# openrex_addon_V1.net
KiCad netlist of a schematic drawn in Altium Designer
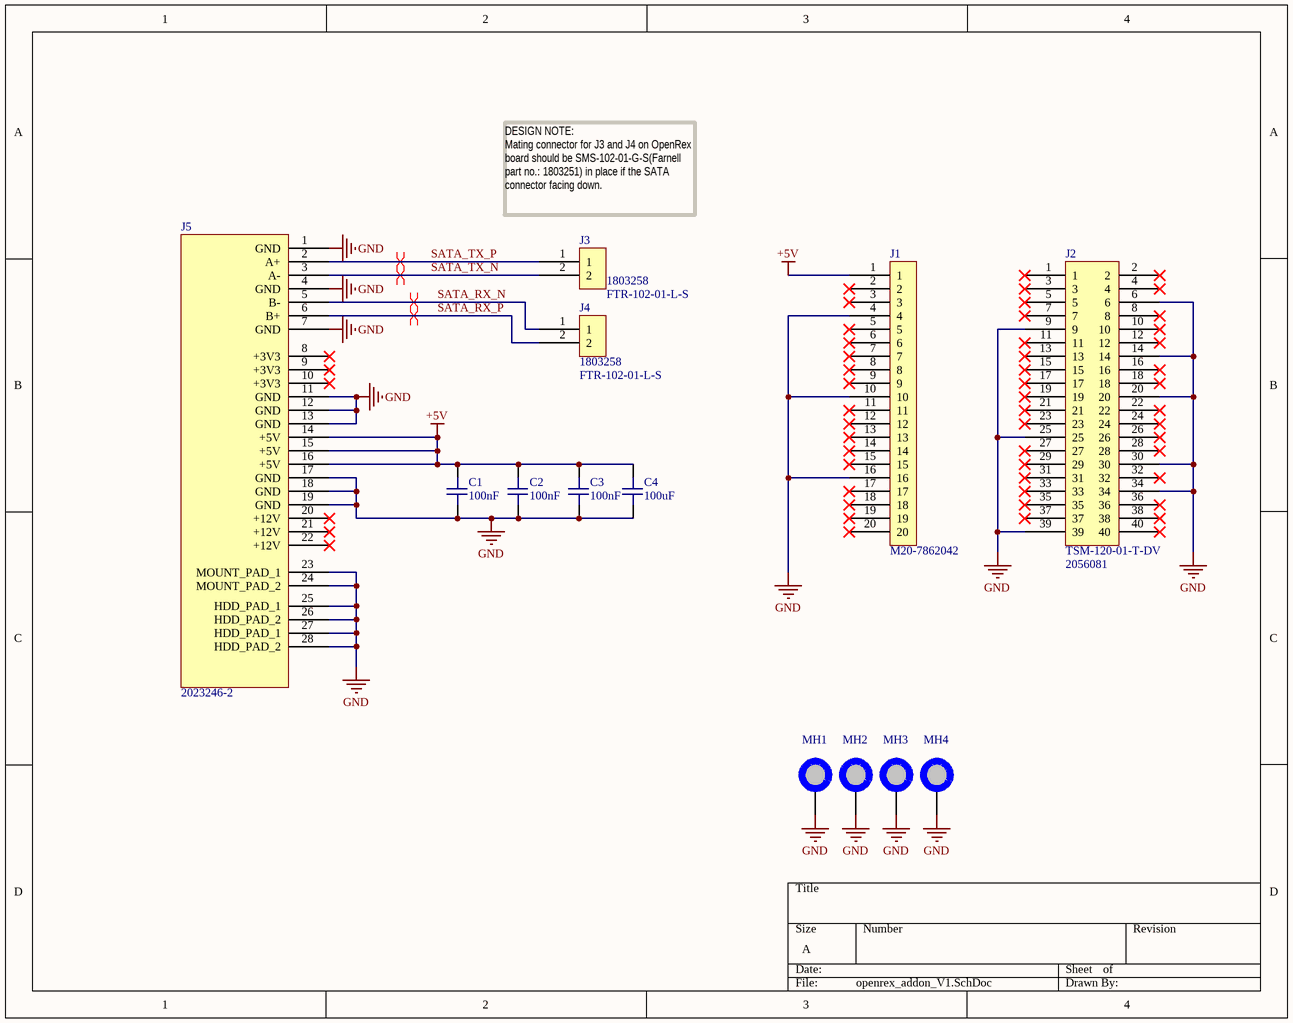
[diagram p0: openrex_addon_V1.SchDoc]

(export (version "E")
  (design (tool "Eeschema 10.0.6"))
  (components
    (comp (ref "C1")
      (value "100nF")
      (footprint "C0805")
      (description "CAP CER 0.1UF 50V X7R 0805")
      (fields
        (field (name "MANUFACTURER") "TDK Corporation")
        (field (name "MANUFACTURER PART NUMBER") "C2012X7R1H104K085AA")
      )
      (libsource (lib "openrex_addon_V1") (part "C2012X7R1H104K085AA"))
    )
    (comp (ref "C2")
      (value "100nF")
      (footprint "C0805")
      (description "CAP CER 0.1UF 50V X7R 0805")
      (fields
        (field (name "MANUFACTURER") "TDK Corporation")
        (field (name "MANUFACTURER PART NUMBER") "C2012X7R1H104K085AA")
      )
      (libsource (lib "openrex_addon_V1") (part "C2012X7R1H104K085AA"))
    )
    (comp (ref "C3")
      (value "100nF")
      (footprint "C0805")
      (description "CAP CER 0.1UF 50V X7R 0805")
      (fields
        (field (name "MANUFACTURER") "TDK Corporation")
        (field (name "MANUFACTURER PART NUMBER") "C2012X7R1H104K085AA")
      )
      (libsource (lib "openrex_addon_V1") (part "C2012X7R1H104K085AA"))
    )
    (comp (ref "C4")
      (value "100uF")
      (footprint "C1206")
      (description "CAP CER 100UF 10V X5R 1206")
      (fields
        (field (name "MANUFACTURER") "TDK Corporation")
        (field (name "MANUFACTURER PART NUMBER") "C3216X5R1A107M160AC")
      )
      (libsource (lib "openrex_addon_V1") (part "C3216X5R1A107M160AC"))
    )
    (comp (ref "J1")
      (value "M20-7862042")
      (footprint "20x1 2.54 Female SMD")
      (description "HARWIN - M20-7862042 - SOCKET, BOTTOM ENTRY, SMT, 20WAY")
      (fields (field (name "MANUFACTURER") "HARWIN"))
      (libsource (lib "openrex_addon_V1") (part "M20-7862042"))
    )
    (comp (ref "J2")
      (value "TSM-120-01-T-DV")
      (footprint "20x2 2.54 Male SMD")
      (description "CONN HEADER 40POS .100\" DBL SMD")
      (fields (field (name "MANUFACTURER") "Samtec Inc.") (field (name "SUPPLIER PART NUMBER 2") "2056081"))
      (libsource (lib "openrex_addon_V1") (part "TSM-120-01-T-DV"))
    )
    (comp (ref "J3")
      (value "FTR-102-01-L-S")
      (footprint "SATA_SIGNAL")
      (description "SMT .050'' STRIPS")
      (fields (field (name "MANUFACTURER") "Samtec Inc.") (field (name "SUPPLIER PART NUMBER 2") "1803258"))
      (libsource (lib "openrex_addon_V1") (part "FTR-102-01-L-S"))
    )
    (comp (ref "J4")
      (value "FTR-102-01-L-S")
      (footprint "SATA_SIGNAL")
      (description "SMT .050'' STRIPS")
      (fields (field (name "MANUFACTURER") "Samtec Inc.") (field (name "SUPPLIER PART NUMBER 2") "1803258"))
      (libsource (lib "openrex_addon_V1") (part "FTR-102-01-L-S"))
    )
    (comp (ref "J5")
      (value "2023246-2")
      (footprint "SATA")
      (description "CONN RECEPT SATA 22POS R/A SMD")
      (fields (field (name "MANUFACTURER") "TE Connectivity AMP Connectors"))
      (libsource (lib "openrex_addon_V1") (part "2023246-2"))
    )
    (comp (ref "MH1")
      (value "MH_7.4MMC_3.2MMD")
      (footprint "MH_7.4MMD_3.2MMD")
      (description "Mounting hole 7.4mm Diameter, 3.2 Drill")
      (libsource (lib "openrex_addon_V1") (part "MH_7.4MMC_3.2MMD"))
    )
    (comp (ref "MH2")
      (value "MH_7.4MMC_3.2MMD")
      (footprint "MH_7.4MMD_3.2MMD")
      (description "Mounting hole 7.4mm Diameter, 3.2 Drill")
      (libsource (lib "openrex_addon_V1") (part "MH_7.4MMC_3.2MMD"))
    )
    (comp (ref "MH3")
      (value "MH_7.4MMC_3.2MMD")
      (footprint "MH_7.4MMD_3.2MMD")
      (description "Mounting hole 7.4mm Diameter, 3.2 Drill")
      (libsource (lib "openrex_addon_V1") (part "MH_7.4MMC_3.2MMD"))
    )
    (comp (ref "MH4")
      (value "MH_7.4MMC_3.2MMD")
      (footprint "MH_7.4MMD_3.2MMD")
      (description "Mounting hole 7.4mm Diameter, 3.2 Drill")
      (libsource (lib "openrex_addon_V1") (part "MH_7.4MMC_3.2MMD"))
    )
  )
  (nets
    (net (code "1") (name "+5V") (class "Default")
      (node (ref "C1") (pin "2") (pinfunction "2_2") (pintype "passive"))
      (node (ref "C2") (pin "2") (pinfunction "2_2") (pintype "passive"))
      (node (ref "C3") (pin "2") (pinfunction "2_2") (pintype "passive"))
      (node (ref "C4") (pin "2") (pinfunction "2_2") (pintype "passive"))
      (node (ref "J1") (pin "1") (pinfunction "1_1") (pintype "passive"))
      (node (ref "J5") (pin "14") (pinfunction "+5V_14") (pintype "passive"))
      (node (ref "J5") (pin "15") (pinfunction "+5V_15") (pintype "passive"))
      (node (ref "J5") (pin "16") (pinfunction "+5V_16") (pintype "passive"))
    )
    (net (code "2") (name "/SATA_RX_N") (class "Default")
      (node (ref "J4") (pin "1") (pinfunction "1_1") (pintype "passive"))
      (node (ref "J5") (pin "5") (pinfunction "B-_5") (pintype "passive"))
    )
    (net (code "3") (name "/SATA_RX_P") (class "Default")
      (node (ref "J4") (pin "2") (pinfunction "2_2") (pintype "passive"))
      (node (ref "J5") (pin "6") (pinfunction "B+_6") (pintype "passive"))
    )
    (net (code "4") (name "/SATA_TX_N") (class "Default")
      (node (ref "J3") (pin "2") (pinfunction "2_2") (pintype "passive"))
      (node (ref "J5") (pin "3") (pinfunction "A-_3") (pintype "passive"))
    )
    (net (code "5") (name "/SATA_TX_P") (class "Default")
      (node (ref "J3") (pin "1") (pinfunction "1_1") (pintype "passive"))
      (node (ref "J5") (pin "2") (pinfunction "A+_2") (pintype "passive"))
    )
    (net (code "6") (name "GND") (class "Default")
      (node (ref "C1") (pin "1") (pinfunction "1_1") (pintype "passive"))
      (node (ref "C2") (pin "1") (pinfunction "1_1") (pintype "passive"))
      (node (ref "C3") (pin "1") (pinfunction "1_1") (pintype "passive"))
      (node (ref "C4") (pin "1") (pinfunction "1_1") (pintype "passive"))
      (node (ref "J1") (pin "10") (pinfunction "10_10") (pintype "passive"))
      (node (ref "J1") (pin "16") (pinfunction "16_16") (pintype "passive"))
      (node (ref "J1") (pin "4") (pinfunction "4_4") (pintype "passive"))
      (node (ref "J2") (pin "14") (pinfunction "14_14") (pintype "passive"))
      (node (ref "J2") (pin "20") (pinfunction "20_20") (pintype "passive"))
      (node (ref "J2") (pin "25") (pinfunction "25_25") (pintype "passive"))
      (node (ref "J2") (pin "30") (pinfunction "30_30") (pintype "passive"))
      (node (ref "J2") (pin "34") (pinfunction "34_34") (pintype "passive"))
      (node (ref "J2") (pin "39") (pinfunction "39_39") (pintype "passive"))
      (node (ref "J2") (pin "6") (pinfunction "6_6") (pintype "passive"))
      (node (ref "J2") (pin "9") (pinfunction "9_9") (pintype "passive"))
      (node (ref "J5") (pin "1") (pinfunction "GND_1") (pintype "passive"))
      (node (ref "J5") (pin "11") (pinfunction "GND_11") (pintype "passive"))
      (node (ref "J5") (pin "12") (pinfunction "GND_12") (pintype "passive"))
      (node (ref "J5") (pin "13") (pinfunction "GND_13") (pintype "passive"))
      (node (ref "J5") (pin "17") (pinfunction "GND_17") (pintype "passive"))
      (node (ref "J5") (pin "18") (pinfunction "GND_18") (pintype "passive"))
      (node (ref "J5") (pin "19") (pinfunction "GND_19") (pintype "passive"))
      (node (ref "J5") (pin "23") (pinfunction "MOUNT_PAD_1_23") (pintype "passive"))
      (node (ref "J5") (pin "24") (pinfunction "MOUNT_PAD_2_24") (pintype "passive"))
      (node (ref "J5") (pin "25") (pinfunction "HDD_PAD_1_25") (pintype "passive"))
      (node (ref "J5") (pin "26") (pinfunction "HDD_PAD_2_26") (pintype "passive"))
      (node (ref "J5") (pin "27") (pinfunction "HDD_PAD_1_27") (pintype "passive"))
      (node (ref "J5") (pin "28") (pinfunction "HDD_PAD_2_28") (pintype "passive"))
      (node (ref "J5") (pin "4") (pinfunction "GND_4") (pintype "passive"))
      (node (ref "J5") (pin "7") (pinfunction "GND_7") (pintype "passive"))
      (node (ref "MH1") (pin "1") (pinfunction "1_1") (pintype "passive"))
      (node (ref "MH2") (pin "1") (pinfunction "1_1") (pintype "passive"))
      (node (ref "MH3") (pin "1") (pinfunction "1_1") (pintype "passive"))
      (node (ref "MH4") (pin "1") (pinfunction "1_1") (pintype "passive"))
    )
    (net (code "7") (name "unconnected-(J1-Pad2)") (class "Default")
      (node (ref "J1") (pin "2") (pinfunction "2_2") (pintype "passive+no_connect"))
    )
    (net (code "8") (name "unconnected-(J1-Pad3)") (class "Default")
      (node (ref "J1") (pin "3") (pinfunction "3_3") (pintype "passive+no_connect"))
    )
    (net (code "9") (name "unconnected-(J1-Pad5)") (class "Default")
      (node (ref "J1") (pin "5") (pinfunction "5_5") (pintype "passive+no_connect"))
    )
    (net (code "10") (name "unconnected-(J1-Pad6)") (class "Default")
      (node (ref "J1") (pin "6") (pinfunction "6_6") (pintype "passive+no_connect"))
    )
    (net (code "11") (name "unconnected-(J1-Pad7)") (class "Default")
      (node (ref "J1") (pin "7") (pinfunction "7_7") (pintype "passive+no_connect"))
    )
    (net (code "12") (name "unconnected-(J1-Pad8)") (class "Default")
      (node (ref "J1") (pin "8") (pinfunction "8_8") (pintype "passive+no_connect"))
    )
    (net (code "13") (name "unconnected-(J1-Pad9)") (class "Default")
      (node (ref "J1") (pin "9") (pinfunction "9_9") (pintype "passive+no_connect"))
    )
    (net (code "14") (name "unconnected-(J1-Pad11)") (class "Default")
      (node (ref "J1") (pin "11") (pinfunction "11_11") (pintype "passive+no_connect"))
    )
    (net (code "15") (name "unconnected-(J1-Pad12)") (class "Default")
      (node (ref "J1") (pin "12") (pinfunction "12_12") (pintype "passive+no_connect"))
    )
    (net (code "16") (name "unconnected-(J1-Pad13)") (class "Default")
      (node (ref "J1") (pin "13") (pinfunction "13_13") (pintype "passive+no_connect"))
    )
    (net (code "17") (name "unconnected-(J1-Pad14)") (class "Default")
      (node (ref "J1") (pin "14") (pinfunction "14_14") (pintype "passive+no_connect"))
    )
    (net (code "18") (name "unconnected-(J1-Pad15)") (class "Default")
      (node (ref "J1") (pin "15") (pinfunction "15_15") (pintype "passive+no_connect"))
    )
    (net (code "19") (name "unconnected-(J1-Pad17)") (class "Default")
      (node (ref "J1") (pin "17") (pinfunction "17_17") (pintype "passive+no_connect"))
    )
    (net (code "20") (name "unconnected-(J1-Pad18)") (class "Default")
      (node (ref "J1") (pin "18") (pinfunction "18_18") (pintype "passive+no_connect"))
    )
    (net (code "21") (name "unconnected-(J1-Pad19)") (class "Default")
      (node (ref "J1") (pin "19") (pinfunction "19_19") (pintype "passive+no_connect"))
    )
    (net (code "22") (name "unconnected-(J1-Pad20)") (class "Default")
      (node (ref "J1") (pin "20") (pinfunction "20_20") (pintype "passive+no_connect"))
    )
    (net (code "23") (name "unconnected-(J2-Pad1)") (class "Default")
      (node (ref "J2") (pin "1") (pinfunction "1_1") (pintype "passive+no_connect"))
    )
    (net (code "24") (name "unconnected-(J2-Pad2)") (class "Default")
      (node (ref "J2") (pin "2") (pinfunction "2_2") (pintype "passive+no_connect"))
    )
    (net (code "25") (name "unconnected-(J2-Pad3)") (class "Default")
      (node (ref "J2") (pin "3") (pinfunction "3_3") (pintype "passive+no_connect"))
    )
    (net (code "26") (name "unconnected-(J2-Pad4)") (class "Default")
      (node (ref "J2") (pin "4") (pinfunction "4_4") (pintype "passive+no_connect"))
    )
    (net (code "27") (name "unconnected-(J2-Pad5)") (class "Default")
      (node (ref "J2") (pin "5") (pinfunction "5_5") (pintype "passive+no_connect"))
    )
    (net (code "28") (name "unconnected-(J2-Pad7)") (class "Default")
      (node (ref "J2") (pin "7") (pinfunction "7_7") (pintype "passive+no_connect"))
    )
    (net (code "29") (name "unconnected-(J2-Pad8)") (class "Default")
      (node (ref "J2") (pin "8") (pinfunction "8_8") (pintype "passive+no_connect"))
    )
    (net (code "30") (name "unconnected-(J2-Pad10)") (class "Default")
      (node (ref "J2") (pin "10") (pinfunction "10_10") (pintype "passive+no_connect"))
    )
    (net (code "31") (name "unconnected-(J2-Pad11)") (class "Default")
      (node (ref "J2") (pin "11") (pinfunction "11_11") (pintype "passive+no_connect"))
    )
    (net (code "32") (name "unconnected-(J2-Pad12)") (class "Default")
      (node (ref "J2") (pin "12") (pinfunction "12_12") (pintype "passive+no_connect"))
    )
    (net (code "33") (name "unconnected-(J2-Pad13)") (class "Default")
      (node (ref "J2") (pin "13") (pinfunction "13_13") (pintype "passive+no_connect"))
    )
    (net (code "34") (name "unconnected-(J2-Pad15)") (class "Default")
      (node (ref "J2") (pin "15") (pinfunction "15_15") (pintype "passive+no_connect"))
    )
    (net (code "35") (name "unconnected-(J2-Pad16)") (class "Default")
      (node (ref "J2") (pin "16") (pinfunction "16_16") (pintype "passive+no_connect"))
    )
    (net (code "36") (name "unconnected-(J2-Pad17)") (class "Default")
      (node (ref "J2") (pin "17") (pinfunction "17_17") (pintype "passive+no_connect"))
    )
    (net (code "37") (name "unconnected-(J2-Pad18)") (class "Default")
      (node (ref "J2") (pin "18") (pinfunction "18_18") (pintype "passive+no_connect"))
    )
    (net (code "38") (name "unconnected-(J2-Pad19)") (class "Default")
      (node (ref "J2") (pin "19") (pinfunction "19_19") (pintype "passive+no_connect"))
    )
    (net (code "39") (name "unconnected-(J2-Pad21)") (class "Default")
      (node (ref "J2") (pin "21") (pinfunction "21_21") (pintype "passive+no_connect"))
    )
    (net (code "40") (name "unconnected-(J2-Pad22)") (class "Default")
      (node (ref "J2") (pin "22") (pinfunction "22_22") (pintype "passive+no_connect"))
    )
    (net (code "41") (name "unconnected-(J2-Pad23)") (class "Default")
      (node (ref "J2") (pin "23") (pinfunction "23_23") (pintype "passive+no_connect"))
    )
    (net (code "42") (name "unconnected-(J2-Pad24)") (class "Default")
      (node (ref "J2") (pin "24") (pinfunction "24_24") (pintype "passive+no_connect"))
    )
    (net (code "43") (name "unconnected-(J2-Pad26)") (class "Default")
      (node (ref "J2") (pin "26") (pinfunction "26_26") (pintype "passive+no_connect"))
    )
    (net (code "44") (name "unconnected-(J2-Pad27)") (class "Default")
      (node (ref "J2") (pin "27") (pinfunction "27_27") (pintype "passive+no_connect"))
    )
    (net (code "45") (name "unconnected-(J2-Pad28)") (class "Default")
      (node (ref "J2") (pin "28") (pinfunction "28_28") (pintype "passive+no_connect"))
    )
    (net (code "46") (name "unconnected-(J2-Pad29)") (class "Default")
      (node (ref "J2") (pin "29") (pinfunction "29_29") (pintype "passive+no_connect"))
    )
    (net (code "47") (name "unconnected-(J2-Pad31)") (class "Default")
      (node (ref "J2") (pin "31") (pinfunction "31_31") (pintype "passive+no_connect"))
    )
    (net (code "48") (name "unconnected-(J2-Pad32)") (class "Default")
      (node (ref "J2") (pin "32") (pinfunction "32_32") (pintype "passive+no_connect"))
    )
    (net (code "49") (name "unconnected-(J2-Pad33)") (class "Default")
      (node (ref "J2") (pin "33") (pinfunction "33_33") (pintype "passive+no_connect"))
    )
    (net (code "50") (name "unconnected-(J2-Pad35)") (class "Default")
      (node (ref "J2") (pin "35") (pinfunction "35_35") (pintype "passive+no_connect"))
    )
    (net (code "51") (name "unconnected-(J2-Pad36)") (class "Default")
      (node (ref "J2") (pin "36") (pinfunction "36_36") (pintype "passive+no_connect"))
    )
    (net (code "52") (name "unconnected-(J2-Pad37)") (class "Default")
      (node (ref "J2") (pin "37") (pinfunction "37_37") (pintype "passive+no_connect"))
    )
    (net (code "53") (name "unconnected-(J2-Pad38)") (class "Default")
      (node (ref "J2") (pin "38") (pinfunction "38_38") (pintype "passive+no_connect"))
    )
    (net (code "54") (name "unconnected-(J2-Pad40)") (class "Default")
      (node (ref "J2") (pin "40") (pinfunction "40_40") (pintype "passive+no_connect"))
    )
    (net (code "55") (name "unconnected-(J5-+3V3-Pad8)") (class "Default")
      (node (ref "J5") (pin "8") (pinfunction "+3V3_8") (pintype "passive+no_connect"))
    )
    (net (code "56") (name "unconnected-(J5-+3V3-Pad9)") (class "Default")
      (node (ref "J5") (pin "9") (pinfunction "+3V3_9") (pintype "passive+no_connect"))
    )
    (net (code "57") (name "unconnected-(J5-+3V3-Pad10)") (class "Default")
      (node (ref "J5") (pin "10") (pinfunction "+3V3_10") (pintype "passive+no_connect"))
    )
    (net (code "58") (name "unconnected-(J5-+12V-Pad20)") (class "Default")
      (node (ref "J5") (pin "20") (pinfunction "+12V_20") (pintype "passive+no_connect"))
    )
    (net (code "59") (name "unconnected-(J5-+12V-Pad21)") (class "Default")
      (node (ref "J5") (pin "21") (pinfunction "+12V_21") (pintype "passive+no_connect"))
    )
    (net (code "60") (name "unconnected-(J5-+12V-Pad22)") (class "Default")
      (node (ref "J5") (pin "22") (pinfunction "+12V_22") (pintype "passive+no_connect"))
    )
  )
)
